# WiFi_Switch.net
KiCad netlist of a schematic drawn in EAGLE
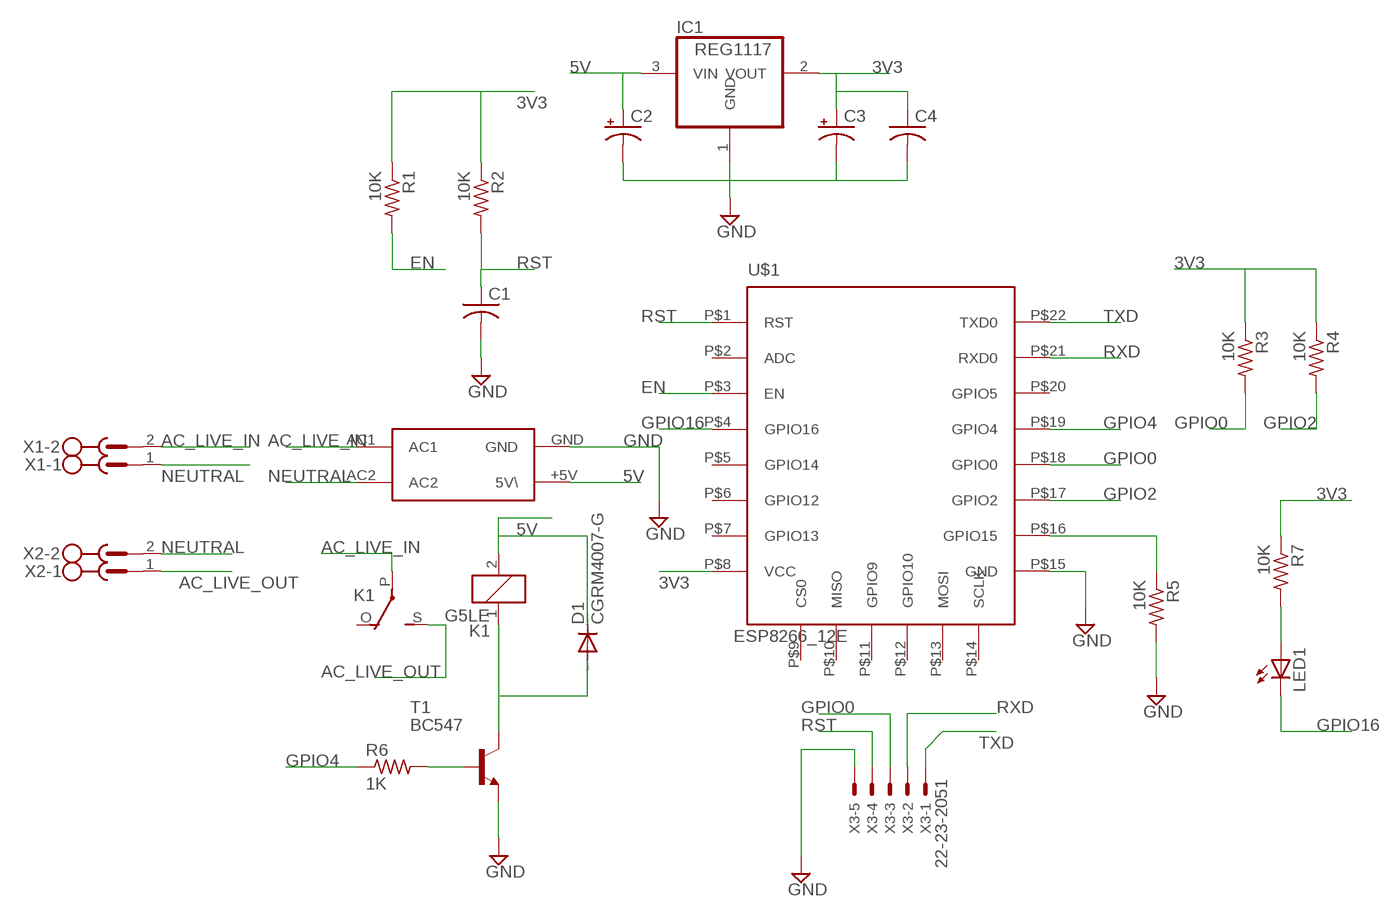
[diagram p0: schematic, sheet 1]

(export (version "E")
  (design (tool "Eeschema 10.0.6"))
  (components
    (comp (ref "C1")
      (value "C-USC1206")
      (footprint "eagle-import:C1206")
      (libsource (lib "eagle-import") (part "C-USC1206"))
    )
    (comp (ref "C2")
      (value "CPOL-USE5-6")
      (footprint "eagle-import:E5-6")
      (libsource (lib "eagle-import") (part "CPOL-USE5-6"))
    )
    (comp (ref "C3")
      (value "CPOL-USE5-6")
      (footprint "eagle-import:E5-6")
      (libsource (lib "eagle-import") (part "CPOL-USE5-6"))
    )
    (comp (ref "C4")
      (value "C-USC1206")
      (footprint "eagle-import:C1206")
      (libsource (lib "eagle-import") (part "C-USC1206"))
    )
    (comp (ref "D1")
      (value "CGRM4007-G")
      (footprint "eagle-import:SOD-123_MINI-SMA")
      (libsource (lib "eagle-import") (part "CGRM400-G7"))
    )
    (comp (ref "IC1")
      (value "REG1117")
      (footprint "eagle-import:SOT223")
      (libsource (lib "eagle-import") (part "REG1117"))
    )
    (comp (ref "K1")
      (value "G5LE")
      (footprint "eagle-import:G5LE")
      (libsource (lib "eagle-import") (part "G5LE"))
    )
    (comp (ref "LED1")
      (value "LED3MM")
      (footprint "eagle-import:LED3MM")
      (libsource (lib "eagle-import") (part "LED3MM"))
    )
    (comp (ref "R1")
      (value "10K")
      (footprint "eagle-import:R1206")
      (libsource (lib "eagle-import") (part "R-US_R1206"))
    )
    (comp (ref "R2")
      (value "10K")
      (footprint "eagle-import:R1206")
      (libsource (lib "eagle-import") (part "R-US_R1206"))
    )
    (comp (ref "R3")
      (value "10K")
      (footprint "eagle-import:R1206")
      (libsource (lib "eagle-import") (part "R-US_R1206"))
    )
    (comp (ref "R4")
      (value "10K")
      (footprint "eagle-import:R1206")
      (libsource (lib "eagle-import") (part "R-US_R1206"))
    )
    (comp (ref "R5")
      (value "10K")
      (footprint "eagle-import:R1206")
      (libsource (lib "eagle-import") (part "R-US_R1206"))
    )
    (comp (ref "R6")
      (value "1K")
      (footprint "eagle-import:R1206")
      (libsource (lib "eagle-import") (part "R-US_R1206"))
    )
    (comp (ref "R7")
      (value "10K")
      (footprint "eagle-import:R1206")
      (libsource (lib "eagle-import") (part "R-US_R1206"))
    )
    (comp (ref "T1")
      (value "BC547")
      (footprint "eagle-import:TO92")
      (libsource (lib "eagle-import") (part "BC547"))
    )
    (comp (ref "U$1")
      (value "ESP8266_12E")
      (footprint "eagle-import:SMT_ESP8266")
      (libsource (lib "eagle-import") (part "ESP8266_12E"))
    )
    (comp (ref "U$2")
      (value "HILINK_SMPS_5V5W")
      (footprint "eagle-import:PCB_MOUNT")
      (libsource (lib "eagle-import") (part "HILINK_SMPS_5V5W"))
    )
    (comp (ref "X1")
      (value "MSTBV2")
      (footprint "eagle-import:MSTBV2")
      (libsource (lib "eagle-import") (part "MSTBV2"))
    )
    (comp (ref "X2")
      (value "MSTBV2")
      (footprint "eagle-import:MSTBV2")
      (libsource (lib "eagle-import") (part "MSTBV2"))
    )
    (comp (ref "X3")
      (value "22-23-2051")
      (footprint "eagle-import:22-23-2051")
      (fields (field (name "MF") "MOLEX"))
      (libsource (lib "eagle-import") (part "22-23-2051"))
    )
  )
  (nets
    (net (code "1") (name "/3V3") (class "Default")
      (node (ref "C3") (pin "+") (pinfunction "+_+") (pintype "passive"))
      (node (ref "C4") (pin "1") (pinfunction "1_1") (pintype "passive"))
      (node (ref "IC1") (pin "2") (pinfunction "VOUT_2") (pintype "output"))
      (node (ref "R1") (pin "1") (pinfunction "1_1") (pintype "passive"))
      (node (ref "R2") (pin "1") (pinfunction "1_1") (pintype "passive"))
      (node (ref "R3") (pin "1") (pinfunction "1_1") (pintype "passive"))
      (node (ref "R4") (pin "1") (pinfunction "1_1") (pintype "passive"))
      (node (ref "R7") (pin "1") (pinfunction "1_1") (pintype "passive"))
      (node (ref "U$1") (pin "P$8") (pinfunction "VCC_P$8") (pintype "bidirectional"))
    )
    (net (code "2") (name "/5V") (class "Default")
      (node (ref "C2") (pin "+") (pinfunction "+_+") (pintype "passive"))
      (node (ref "D1") (pin "C") (pinfunction "C_C") (pintype "passive"))
      (node (ref "IC1") (pin "3") (pinfunction "VIN_3") (pintype "input"))
      (node (ref "K1") (pin "2") (pinfunction "2_2") (pintype "passive"))
      (node (ref "U$2") (pin "+5V") (pinfunction "5V\\_+5V") (pintype "bidirectional"))
    )
    (net (code "3") (name "/AC_LIVE_IN") (class "Default")
      (node (ref "K1") (pin "P") (pinfunction "P_P") (pintype "passive"))
      (node (ref "U$2") (pin "AC1") (pinfunction "AC1_AC1") (pintype "bidirectional"))
      (node (ref "X1") (pin "2") (pinfunction "SK_2") (pintype "passive"))
    )
    (net (code "4") (name "/AC_LIVE_OUT") (class "Default")
      (node (ref "K1") (pin "S") (pinfunction "S_S") (pintype "passive"))
      (node (ref "X2") (pin "1") (pinfunction "SK_1") (pintype "passive"))
    )
    (net (code "5") (name "/EN") (class "Default")
      (node (ref "R1") (pin "2") (pinfunction "2_2") (pintype "passive"))
      (node (ref "U$1") (pin "P$3") (pinfunction "EN_P$3") (pintype "bidirectional"))
    )
    (net (code "6") (name "/GPIO0") (class "Default")
      (node (ref "R3") (pin "2") (pinfunction "2_2") (pintype "passive"))
      (node (ref "U$1") (pin "P$18") (pinfunction "GPIO0_P$18") (pintype "bidirectional"))
      (node (ref "X3") (pin "3") (pinfunction "S_3") (pintype "passive"))
    )
    (net (code "7") (name "/GPIO2") (class "Default")
      (node (ref "R4") (pin "2") (pinfunction "2_2") (pintype "passive"))
      (node (ref "U$1") (pin "P$17") (pinfunction "GPIO2_P$17") (pintype "bidirectional"))
    )
    (net (code "8") (name "/GPIO4") (class "Default")
      (node (ref "R6") (pin "1") (pinfunction "1_1") (pintype "passive"))
      (node (ref "U$1") (pin "P$19") (pinfunction "GPIO4_P$19") (pintype "bidirectional"))
    )
    (net (code "9") (name "/GPIO16") (class "Default")
      (node (ref "LED1") (pin "K") (pinfunction "C_K") (pintype "passive"))
      (node (ref "U$1") (pin "P$4") (pinfunction "GPIO16_P$4") (pintype "bidirectional"))
    )
    (net (code "10") (name "/NEUTRAL") (class "Default")
      (node (ref "U$2") (pin "AC2") (pinfunction "AC2_AC2") (pintype "bidirectional"))
      (node (ref "X1") (pin "1") (pinfunction "SK_1") (pintype "passive"))
      (node (ref "X2") (pin "2") (pinfunction "SK_2") (pintype "passive"))
    )
    (net (code "11") (name "/RST") (class "Default")
      (node (ref "C1") (pin "1") (pinfunction "1_1") (pintype "passive"))
      (node (ref "R2") (pin "2") (pinfunction "2_2") (pintype "passive"))
      (node (ref "U$1") (pin "P$1") (pinfunction "RST_P$1") (pintype "bidirectional"))
      (node (ref "X3") (pin "4") (pinfunction "S_4") (pintype "passive"))
    )
    (net (code "12") (name "/RXD") (class "Default")
      (node (ref "U$1") (pin "P$21") (pinfunction "RXD0_P$21") (pintype "bidirectional"))
      (node (ref "X3") (pin "2") (pinfunction "S_2") (pintype "passive"))
    )
    (net (code "13") (name "/TXD") (class "Default")
      (node (ref "U$1") (pin "P$22") (pinfunction "TXD0_P$22") (pintype "bidirectional"))
      (node (ref "X3") (pin "1") (pinfunction "S_1") (pintype "passive"))
    )
    (net (code "14") (name "GND") (class "Default")
      (node (ref "C1") (pin "2") (pinfunction "2_2") (pintype "passive"))
      (node (ref "C2") (pin "-") (pinfunction "-_-") (pintype "passive"))
      (node (ref "C3") (pin "-") (pinfunction "-_-") (pintype "passive"))
      (node (ref "C4") (pin "2") (pinfunction "2_2") (pintype "passive"))
      (node (ref "IC1") (pin "1") (pinfunction "GND_1") (pintype "power_in"))
      (node (ref "R5") (pin "2") (pinfunction "2_2") (pintype "passive"))
      (node (ref "T1") (pin "1") (pinfunction "E_1") (pintype "passive"))
      (node (ref "U$1") (pin "P$15") (pinfunction "GND_P$15") (pintype "bidirectional"))
      (node (ref "U$2") (pin "GND") (pinfunction "GND_GND") (pintype "bidirectional"))
      (node (ref "X3") (pin "5") (pinfunction "S_5") (pintype "passive"))
    )
    (net (code "15") (name "Net-(LED1-PadA)") (class "Default")
      (node (ref "LED1") (pin "A") (pinfunction "A_A") (pintype "passive"))
      (node (ref "R7") (pin "2") (pinfunction "2_2") (pintype "passive"))
    )
    (net (code "16") (name "Net-(T1-B)") (class "Default")
      (node (ref "R6") (pin "2") (pinfunction "2_2") (pintype "passive"))
      (node (ref "T1") (pin "2") (pinfunction "B_2") (pintype "passive"))
    )
    (net (code "17") (name "Net-(T1-C)") (class "Default")
      (node (ref "D1") (pin "A") (pinfunction "A_A") (pintype "passive"))
      (node (ref "K1") (pin "1") (pinfunction "1_1") (pintype "passive"))
      (node (ref "T1") (pin "3") (pinfunction "C_3") (pintype "passive"))
    )
    (net (code "18") (name "Net-(U$1-GPIO15)") (class "Default")
      (node (ref "R5") (pin "1") (pinfunction "1_1") (pintype "passive"))
      (node (ref "U$1") (pin "P$16") (pinfunction "GPIO15_P$16") (pintype "bidirectional"))
    )
    (net (code "19") (name "unconnected-(K1-PadO)") (class "Default")
      (node (ref "K1") (pin "O") (pinfunction "O_O") (pintype "passive"))
    )
    (net (code "20") (name "unconnected-(U$1-ADC-PadP$2)") (class "Default")
      (node (ref "U$1") (pin "P$2") (pinfunction "ADC_P$2") (pintype "bidirectional"))
    )
    (net (code "21") (name "unconnected-(U$1-CS0-PadP$9)") (class "Default")
      (node (ref "U$1") (pin "P$9") (pinfunction "CS0_P$9") (pintype "bidirectional"))
    )
    (net (code "22") (name "unconnected-(U$1-GPIO5-PadP$20)") (class "Default")
      (node (ref "U$1") (pin "P$20") (pinfunction "GPIO5_P$20") (pintype "bidirectional"))
    )
    (net (code "23") (name "unconnected-(U$1-GPIO9-PadP$11)") (class "Default")
      (node (ref "U$1") (pin "P$11") (pinfunction "GPIO9_P$11") (pintype "bidirectional"))
    )
    (net (code "24") (name "unconnected-(U$1-GPIO10-PadP$12)") (class "Default")
      (node (ref "U$1") (pin "P$12") (pinfunction "GPIO10_P$12") (pintype "bidirectional"))
    )
    (net (code "25") (name "unconnected-(U$1-GPIO12-PadP$6)") (class "Default")
      (node (ref "U$1") (pin "P$6") (pinfunction "GPIO12_P$6") (pintype "bidirectional"))
    )
    (net (code "26") (name "unconnected-(U$1-GPIO13-PadP$7)") (class "Default")
      (node (ref "U$1") (pin "P$7") (pinfunction "GPIO13_P$7") (pintype "bidirectional"))
    )
    (net (code "27") (name "unconnected-(U$1-GPIO14-PadP$5)") (class "Default")
      (node (ref "U$1") (pin "P$5") (pinfunction "GPIO14_P$5") (pintype "bidirectional"))
    )
    (net (code "28") (name "unconnected-(U$1-MISO-PadP$10)") (class "Default")
      (node (ref "U$1") (pin "P$10") (pinfunction "MISO_P$10") (pintype "bidirectional"))
    )
    (net (code "29") (name "unconnected-(U$1-MOSI-PadP$13)") (class "Default")
      (node (ref "U$1") (pin "P$13") (pinfunction "MOSI_P$13") (pintype "bidirectional"))
    )
    (net (code "30") (name "unconnected-(U$1-SCLK-PadP$14)") (class "Default")
      (node (ref "U$1") (pin "P$14") (pinfunction "SCLK_P$14") (pintype "bidirectional"))
    )
  )
)
